# Current_Voltage-acq.net
KiCad netlist of a schematic drawn in Altium Designer
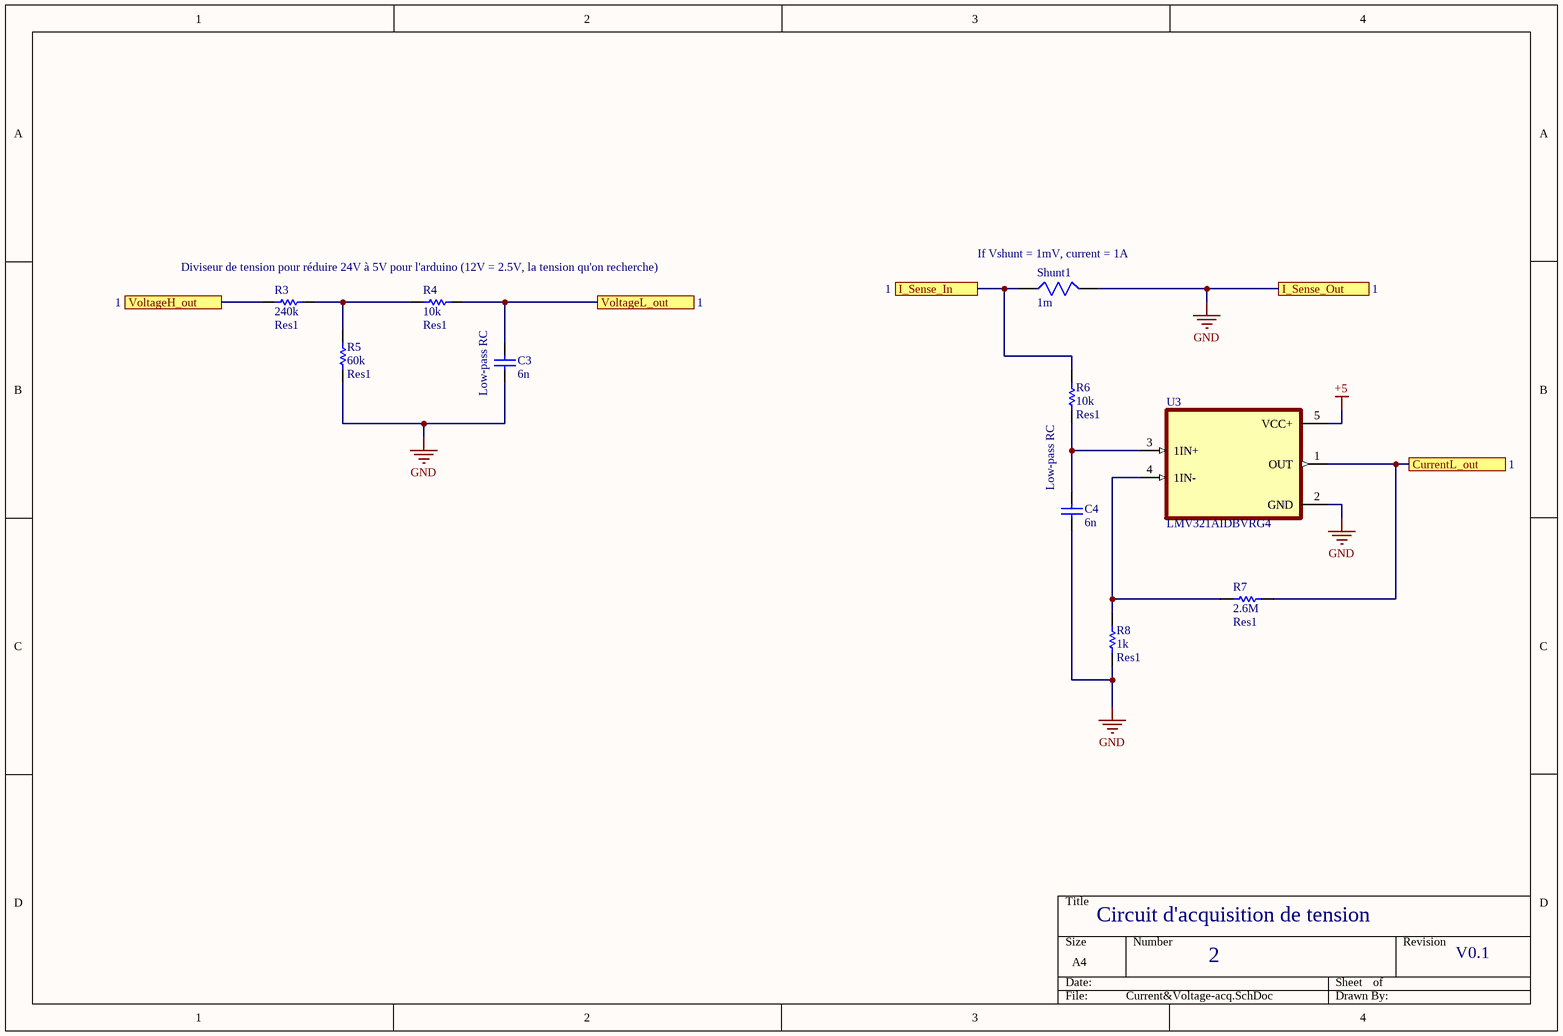
[diagram p0: Current&Voltage-acq.SchDoc]

(export (version "E")
  (design (tool "Eeschema 10.0.6"))
  (components
    (comp (ref "C3")
      (value "6n")
      (footprint "C1206")
      (description "Capacitor (Semiconductor SIM Model)")
      (fields (field (name "Comment") "Ceramic Capacitor") (field (name "PUBLISHER") "Altium Limited"))
      (libsource (lib "Miscellaneous Devices") (part "Cap Semi"))
    )
    (comp (ref "C4")
      (value "6n")
      (footprint "C1206")
      (description "Capacitor (Semiconductor SIM Model)")
      (fields (field (name "Comment") "Ceramic Capacitor") (field (name "PUBLISHER") "Altium Limited"))
      (libsource (lib "Miscellaneous Devices") (part "Cap Semi"))
    )
    (comp (ref "R3")
      (value "Res1")
      (footprint "AXIAL-0.3")
      (description "Resistor")
      (fields (field (name "ALTIUM_VALUE") "240k") (field (name "PUBLISHER") "Altium Limited"))
      (libsource (lib "Miscellaneous Devices") (part "Res1"))
    )
    (comp (ref "R4")
      (value "Res1")
      (footprint "AXIAL-0.3")
      (description "Resistor")
      (fields (field (name "ALTIUM_VALUE") "10k") (field (name "PUBLISHER") "Altium Limited"))
      (libsource (lib "Miscellaneous Devices") (part "Res1"))
    )
    (comp (ref "R5")
      (value "Res1")
      (footprint "AXIAL-0.3")
      (description "Resistor")
      (fields (field (name "ALTIUM_VALUE") "60k") (field (name "PUBLISHER") "Altium Limited"))
      (libsource (lib "Miscellaneous Devices") (part "Res1"))
    )
    (comp (ref "R6")
      (value "Res1")
      (footprint "AXIAL-0.3")
      (description "Resistor")
      (fields (field (name "ALTIUM_VALUE") "10k") (field (name "PUBLISHER") "Altium Limited"))
      (libsource (lib "Miscellaneous Devices") (part "Res1"))
    )
    (comp (ref "R7")
      (value "Res1")
      (footprint "AXIAL-0.3")
      (description "Resistor")
      (fields (field (name "ALTIUM_VALUE") "2.6M") (field (name "PUBLISHER") "Altium Limited"))
      (libsource (lib "Miscellaneous Devices") (part "Res1"))
    )
    (comp (ref "R8")
      (value "Res1")
      (footprint "AXIAL-0.3")
      (description "Resistor")
      (fields (field (name "ALTIUM_VALUE") "1k") (field (name "PUBLISHER") "Altium Limited"))
      (libsource (lib "Miscellaneous Devices") (part "Res1"))
    )
    (comp (ref "Shunt1")
      (value "1m")
      (footprint "resistor_1206")
      (libsource (lib "A25_Projet_conv_CC_Library") (part "resistor"))
    )
    (comp (ref "U3")
      (value "LMV321AIDBVRG4")
      (footprint "SOT95P280X145-5N")
      (fields (field (name "MF") "Texas Instruments") (field (name "MP") "LMV321IDBVRG4"))
      (libsource (lib "A25_Projet_conv_CC_Library") (part "LMV321AIDBVRG4"))
    )
  )
  (nets
    (net (code "1") (name "+5") (class "Default")
      (node (ref "U3") (pin "5") (pinfunction "VCC+_5") (pintype "power_in"))
    )
    (net (code "2") (name "/CurrentL_out") (class "Default")
      (node (ref "R7") (pin "2") (pinfunction "2_2") (pintype "passive"))
      (node (ref "U3") (pin "1") (pinfunction "OUT_1") (pintype "output"))
    )
    (net (code "3") (name "/I_Sense_In") (class "Default")
      (node (ref "R6") (pin "1") (pinfunction "1_1") (pintype "passive"))
      (node (ref "Shunt1") (pin "1") (pinfunction "1_1") (pintype "passive"))
    )
    (net (code "4") (name "/VoltageH_out") (class "Default")
      (node (ref "R3") (pin "1") (pinfunction "1_1") (pintype "passive"))
    )
    (net (code "5") (name "/VoltageL_out") (class "Default")
      (node (ref "C3") (pin "2") (pinfunction "2_2") (pintype "passive"))
      (node (ref "R4") (pin "2") (pinfunction "2_2") (pintype "passive"))
    )
    (net (code "6") (name "GND") (class "Default")
      (node (ref "C3") (pin "1") (pinfunction "1_1") (pintype "passive"))
      (node (ref "C4") (pin "1") (pinfunction "1_1") (pintype "passive"))
      (node (ref "R5") (pin "2") (pinfunction "2_2") (pintype "passive"))
      (node (ref "R8") (pin "2") (pinfunction "2_2") (pintype "passive"))
      (node (ref "Shunt1") (pin "2") (pinfunction "2_2") (pintype "passive"))
      (node (ref "U3") (pin "2") (pinfunction "GND_2") (pintype "power_in"))
    )
    (net (code "7") (name "Net-(R3-Pad2)") (class "Default")
      (node (ref "R3") (pin "2") (pinfunction "2_2") (pintype "passive"))
      (node (ref "R4") (pin "1") (pinfunction "1_1") (pintype "passive"))
      (node (ref "R5") (pin "1") (pinfunction "1_1") (pintype "passive"))
    )
    (net (code "8") (name "Net-(U3-1IN+)") (class "Default")
      (node (ref "C4") (pin "2") (pinfunction "2_2") (pintype "passive"))
      (node (ref "R6") (pin "2") (pinfunction "2_2") (pintype "passive"))
      (node (ref "U3") (pin "3") (pinfunction "1IN+_3") (pintype "input"))
    )
    (net (code "9") (name "Net-(U3-1IN-)") (class "Default")
      (node (ref "R7") (pin "1") (pinfunction "1_1") (pintype "passive"))
      (node (ref "R8") (pin "1") (pinfunction "1_1") (pintype "passive"))
      (node (ref "U3") (pin "4") (pinfunction "1IN-_4") (pintype "input"))
    )
  )
)
